# USB_9.net
KiCad netlist of a schematic drawn in Altium Designer
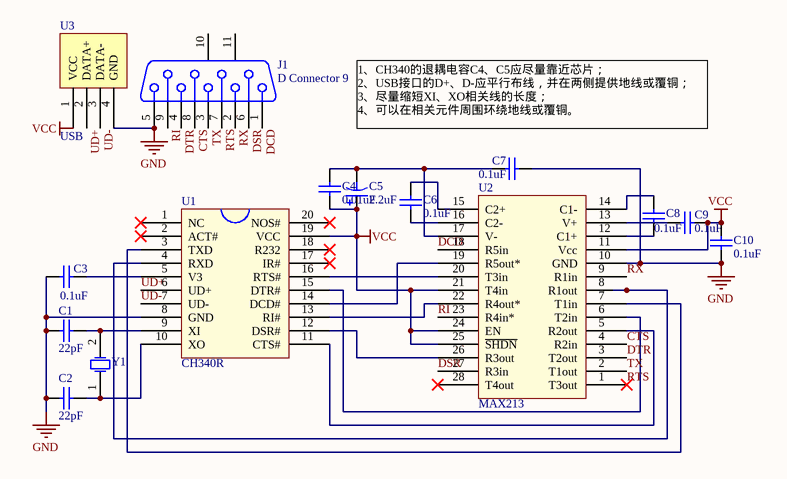
[diagram p0: USB转9线串口.SchDoc]

(export (version "E")
  (design (tool "Eeschema 10.0.6"))
  (components
    (comp (ref "C1")
      (value "22pF")
      (footprint "RAD-0.3")
      (description "Capacitor")
      (fields (field (name "PUBLISHER") "Altium Limited"))
      (libsource (lib "Miscellaneous Devices") (part "Cap"))
    )
    (comp (ref "C2")
      (value "22pF")
      (footprint "RAD-0.3")
      (description "Capacitor")
      (fields (field (name "PUBLISHER") "Altium Limited"))
      (libsource (lib "Miscellaneous Devices") (part "Cap"))
    )
    (comp (ref "C3")
      (value "0.1uF")
      (footprint "RAD-0.3")
      (description "Capacitor")
      (fields (field (name "PUBLISHER") "Altium Limited"))
      (libsource (lib "Miscellaneous Devices") (part "Cap"))
    )
    (comp (ref "C4")
      (value "0.01uF")
      (footprint "RAD-0.3")
      (description "Capacitor")
      (fields (field (name "PUBLISHER") "Altium Limited"))
      (libsource (lib "Miscellaneous Devices") (part "Cap"))
    )
    (comp (ref "C5")
      (value "2.2uF")
      (footprint "RB7.6-15")
      (description "Polarized Capacitor (Radial)")
      (fields (field (name "Comment") "Cap Pol1") (field (name "PUBLISHER") "Altium Limited"))
      (libsource (lib "Miscellaneous Devices") (part "Cap Pol1"))
    )
    (comp (ref "C6")
      (value "0.1uF")
      (footprint "RAD-0.3")
      (description "Capacitor")
      (fields (field (name "PUBLISHER") "Altium Limited"))
      (libsource (lib "Miscellaneous Devices") (part "Cap"))
    )
    (comp (ref "C7")
      (value "0.1uF")
      (footprint "RAD-0.3")
      (description "Capacitor")
      (fields (field (name "PUBLISHER") "Altium Limited"))
      (libsource (lib "Miscellaneous Devices") (part "Cap"))
    )
    (comp (ref "C8")
      (value "0.1uF")
      (footprint "RAD-0.3")
      (description "Capacitor")
      (fields (field (name "PUBLISHER") "Altium Limited"))
      (libsource (lib "Miscellaneous Devices") (part "Cap"))
    )
    (comp (ref "C9")
      (value "0.1uF")
      (footprint "RAD-0.3")
      (description "Capacitor")
      (fields (field (name "PUBLISHER") "Altium Limited"))
      (libsource (lib "Miscellaneous Devices") (part "Cap"))
    )
    (comp (ref "C10")
      (value "0.1uF")
      (footprint "RAD-0.3")
      (description "Capacitor")
      (fields (field (name "PUBLISHER") "Altium Limited"))
      (libsource (lib "Miscellaneous Devices") (part "Cap"))
    )
    (comp (ref "J1")
      (value "D Connector 9")
      (footprint "DSUB1.385-2H9")
      (description "Receptacle Assembly, 9 Position, Right Angle")
      (fields (field (name "PUBLISHER") "Altium Limited"))
      (libsource (lib "自定义库") (part "D Connector 9"))
    )
    (comp (ref "U1") (value "CH340R") (footprint "SSOP-20") (libsource (lib "自定义库") (part "CH340R")))
    (comp (ref "U2") (value "MAX213") (footprint "SSOP-28") (libsource (lib "自定义库") (part "MAX213")))
    (comp (ref "U3") (value "USB") (footprint "USB-A") (libsource (lib "自定义库") (part "USB")))
    (comp (ref "Y1")
      (value "XTAL")
      (footprint "R38")
      (description "Crystal Oscillator")
      (fields (field (name "PUBLISHER") "Altium Limited"))
      (libsource (lib "自定义库") (part "XTAL"))
    )
  )
  (nets
    (net (code "1") (name "/CTS") (class "Default")
      (node (ref "J1") (pin "8") (pinfunction "8_8") (pintype "passive"))
      (node (ref "U2") (pin "4") (pinfunction "R2in_4") (pintype "passive"))
    )
    (net (code "2") (name "/DCD") (class "Default")
      (node (ref "J1") (pin "1") (pinfunction "1_1") (pintype "passive"))
      (node (ref "U2") (pin "18") (pinfunction "R5in_18") (pintype "passive"))
    )
    (net (code "3") (name "/DSR") (class "Default")
      (node (ref "J1") (pin "6") (pinfunction "6_6") (pintype "passive"))
      (node (ref "U2") (pin "27") (pinfunction "R3in_27") (pintype "passive"))
    )
    (net (code "4") (name "/DTR") (class "Default")
      (node (ref "J1") (pin "4") (pinfunction "4_4") (pintype "passive"))
      (node (ref "U2") (pin "3") (pinfunction "T2out_3") (pintype "passive"))
    )
    (net (code "5") (name "/RI") (class "Default")
      (node (ref "J1") (pin "9") (pinfunction "9_9") (pintype "passive"))
      (node (ref "U2") (pin "23") (pinfunction "R4in*_23") (pintype "passive"))
    )
    (net (code "6") (name "/RTS") (class "Default")
      (node (ref "J1") (pin "7") (pinfunction "7_7") (pintype "passive"))
      (node (ref "U2") (pin "1") (pinfunction "T3out_1") (pintype "passive"))
    )
    (net (code "7") (name "/RX") (class "Default")
      (node (ref "J1") (pin "2") (pinfunction "2_2") (pintype "passive"))
      (node (ref "U2") (pin "9") (pinfunction "R1in_9") (pintype "passive"))
    )
    (net (code "8") (name "/TX") (class "Default")
      (node (ref "J1") (pin "3") (pinfunction "3_3") (pintype "passive"))
      (node (ref "U2") (pin "2") (pinfunction "T1out_2") (pintype "passive"))
    )
    (net (code "9") (name "/UD+") (class "Default")
      (node (ref "U1") (pin "6") (pinfunction "UD+_6") (pintype "passive"))
      (node (ref "U3") (pin "2") (pinfunction "DATA+_2") (pintype "passive"))
    )
    (net (code "10") (name "/UD-") (class "Default")
      (node (ref "U1") (pin "7") (pinfunction "UD-_7") (pintype "passive"))
      (node (ref "U3") (pin "3") (pinfunction "DATA-_3") (pintype "passive"))
    )
    (net (code "11") (name "GND") (class "Default")
      (node (ref "C1") (pin "2") (pinfunction "2_2") (pintype "passive"))
      (node (ref "C10") (pin "1") (pinfunction "1_1") (pintype "passive"))
      (node (ref "C2") (pin "2") (pinfunction "2_2") (pintype "passive"))
      (node (ref "C3") (pin "1") (pinfunction "1_1") (pintype "passive"))
      (node (ref "C7") (pin "2") (pinfunction "2_2") (pintype "passive"))
      (node (ref "J1") (pin "5") (pinfunction "5_5") (pintype "passive"))
      (node (ref "U1") (pin "8") (pinfunction "GND_8") (pintype "passive"))
      (node (ref "U2") (pin "10") (pinfunction "GND_10") (pintype "passive"))
      (node (ref "U3") (pin "4") (pinfunction "GND_4") (pintype "passive"))
    )
    (net (code "12") (name "Net-(U1-CTS#)") (class "Default")
      (node (ref "U1") (pin "11") (pinfunction "CTS#_11") (pintype "passive"))
      (node (ref "U2") (pin "5") (pinfunction "R2out_5") (pintype "passive"))
    )
    (net (code "13") (name "Net-(U1-DCD#)") (class "Default")
      (node (ref "U1") (pin "14") (pinfunction "DCD#_14") (pintype "passive"))
      (node (ref "U2") (pin "19") (pinfunction "R5out*_19") (pintype "passive"))
    )
    (net (code "14") (name "Net-(U1-DSR#)") (class "Default")
      (node (ref "U1") (pin "12") (pinfunction "DSR#_12") (pintype "passive"))
      (node (ref "U2") (pin "26") (pinfunction "R3out_26") (pintype "passive"))
    )
    (net (code "15") (name "Net-(U1-DTR#)") (class "Default")
      (node (ref "U1") (pin "15") (pinfunction "DTR#_15") (pintype "passive"))
      (node (ref "U2") (pin "6") (pinfunction "T2in_6") (pintype "passive"))
    )
    (net (code "16") (name "Net-(U1-RI#)") (class "Default")
      (node (ref "U1") (pin "13") (pinfunction "RI#_13") (pintype "passive"))
      (node (ref "U2") (pin "22") (pinfunction "R4out*_22") (pintype "passive"))
    )
    (net (code "17") (name "Net-(U1-RTS#)") (class "Default")
      (node (ref "U1") (pin "16") (pinfunction "RTS#_16") (pintype "passive"))
      (node (ref "U2") (pin "20") (pinfunction "T3in_20") (pintype "passive"))
    )
    (net (code "18") (name "Net-(U1-RXD)") (class "Default")
      (node (ref "U1") (pin "4") (pinfunction "RXD_4") (pintype "passive"))
      (node (ref "U2") (pin "8") (pinfunction "R1out_8") (pintype "passive"))
    )
    (net (code "19") (name "Net-(U1-TXD)") (class "Default")
      (node (ref "U1") (pin "3") (pinfunction "TXD_3") (pintype "passive"))
      (node (ref "U2") (pin "7") (pinfunction "T1in_7") (pintype "passive"))
    )
    (net (code "20") (name "Net-(U1-V3)") (class "Default")
      (node (ref "C3") (pin "2") (pinfunction "2_2") (pintype "passive"))
      (node (ref "U1") (pin "5") (pinfunction "V3_5") (pintype "passive"))
    )
    (net (code "21") (name "Net-(U1-XI)") (class "Default")
      (node (ref "C1") (pin "1") (pinfunction "1_1") (pintype "passive"))
      (node (ref "U1") (pin "9") (pinfunction "XI_9") (pintype "passive"))
      (node (ref "Y1") (pin "2") (pinfunction "OSC2_2") (pintype "passive"))
    )
    (net (code "22") (name "Net-(U1-XO)") (class "Default")
      (node (ref "C2") (pin "1") (pinfunction "1_1") (pintype "passive"))
      (node (ref "U1") (pin "10") (pinfunction "XO_10") (pintype "passive"))
      (node (ref "Y1") (pin "1") (pinfunction "OSC1_1") (pintype "passive"))
    )
    (net (code "23") (name "Net-(U2-C1+)") (class "Default")
      (node (ref "C8") (pin "1") (pinfunction "1_1") (pintype "passive"))
      (node (ref "U2") (pin "12") (pinfunction "C1+_12") (pintype "passive"))
    )
    (net (code "24") (name "Net-(U2-C1-)") (class "Default")
      (node (ref "C8") (pin "2") (pinfunction "2_2") (pintype "passive"))
      (node (ref "U2") (pin "14") (pinfunction "C1-_14") (pintype "passive"))
    )
    (net (code "25") (name "Net-(U2-C2+)") (class "Default")
      (node (ref "C6") (pin "2") (pinfunction "2_2") (pintype "passive"))
      (node (ref "U2") (pin "15") (pinfunction "C2+_15") (pintype "passive"))
    )
    (net (code "26") (name "Net-(U2-C2-)") (class "Default")
      (node (ref "C6") (pin "1") (pinfunction "1_1") (pintype "passive"))
      (node (ref "U2") (pin "16") (pinfunction "C2-_16") (pintype "passive"))
    )
    (net (code "27") (name "Net-(U2-V+)") (class "Default")
      (node (ref "C9") (pin "1") (pinfunction "1_1") (pintype "passive"))
      (node (ref "U2") (pin "13") (pinfunction "V+_13") (pintype "passive"))
    )
    (net (code "28") (name "Net-(U2-V-)") (class "Default")
      (node (ref "C4") (pin "2") (pinfunction "2_2") (pintype "passive"))
      (node (ref "C5") (pin "2") (pinfunction "2_2") (pintype "passive"))
      (node (ref "C7") (pin "1") (pinfunction "1_1") (pintype "passive"))
      (node (ref "U2") (pin "17") (pinfunction "V-_17") (pintype "passive"))
    )
    (net (code "29") (name "VCC") (class "Default")
      (node (ref "C10") (pin "2") (pinfunction "2_2") (pintype "passive"))
      (node (ref "C4") (pin "1") (pinfunction "1_1") (pintype "passive"))
      (node (ref "C5") (pin "1") (pinfunction "1_1") (pintype "passive"))
      (node (ref "C9") (pin "2") (pinfunction "2_2") (pintype "passive"))
      (node (ref "U1") (pin "19") (pinfunction "VCC_19") (pintype "passive"))
      (node (ref "U2") (pin "11") (pinfunction "Vcc_11") (pintype "passive"))
      (node (ref "U2") (pin "21") (pinfunction "T4in_21") (pintype "passive"))
      (node (ref "U2") (pin "24") (pinfunction "EN_24") (pintype "passive"))
      (node (ref "U2") (pin "25") (pinfunction "~{SHDN}_25") (pintype "passive"))
      (node (ref "U3") (pin "1") (pinfunction "VCC_1") (pintype "passive"))
    )
    (net (code "30") (name "unconnected-(J1-MH1-Pad10)") (class "Default")
      (node (ref "J1") (pin "10") (pinfunction "MH1_10") (pintype "passive"))
    )
    (net (code "31") (name "unconnected-(J1-MH2-Pad11)") (class "Default")
      (node (ref "J1") (pin "11") (pinfunction "MH2_11") (pintype "passive"))
    )
    (net (code "32") (name "unconnected-(U1-ACT#-Pad2)") (class "Default")
      (node (ref "U1") (pin "2") (pinfunction "ACT#_2") (pintype "passive+no_connect"))
    )
    (net (code "33") (name "unconnected-(U1-IR#-Pad17)") (class "Default")
      (node (ref "U1") (pin "17") (pinfunction "IR#_17") (pintype "passive+no_connect"))
    )
    (net (code "34") (name "unconnected-(U1-NC-Pad1)") (class "Default")
      (node (ref "U1") (pin "1") (pinfunction "NC_1") (pintype "passive+no_connect"))
    )
    (net (code "35") (name "unconnected-(U1-NOS#-Pad20)") (class "Default")
      (node (ref "U1") (pin "20") (pinfunction "NOS#_20") (pintype "passive+no_connect"))
    )
    (net (code "36") (name "unconnected-(U1-R232-Pad18)") (class "Default")
      (node (ref "U1") (pin "18") (pinfunction "R232_18") (pintype "passive+no_connect"))
    )
    (net (code "37") (name "unconnected-(U2-T4out-Pad28)") (class "Default")
      (node (ref "U2") (pin "28") (pinfunction "T4out_28") (pintype "passive+no_connect"))
    )
    (net (code "38") (name "unconnected-(U3-NC-Pad5)") (class "Default")
      (node (ref "U3") (pin "5") (pinfunction "NC_5") (pintype "passive"))
    )
    (net (code "39") (name "unconnected-(U3-NC-Pad6)") (class "Default")
      (node (ref "U3") (pin "6") (pinfunction "NC_6") (pintype "passive"))
    )
  )
)
